# STM32.net
KiCad netlist of a schematic drawn in Altium Designer
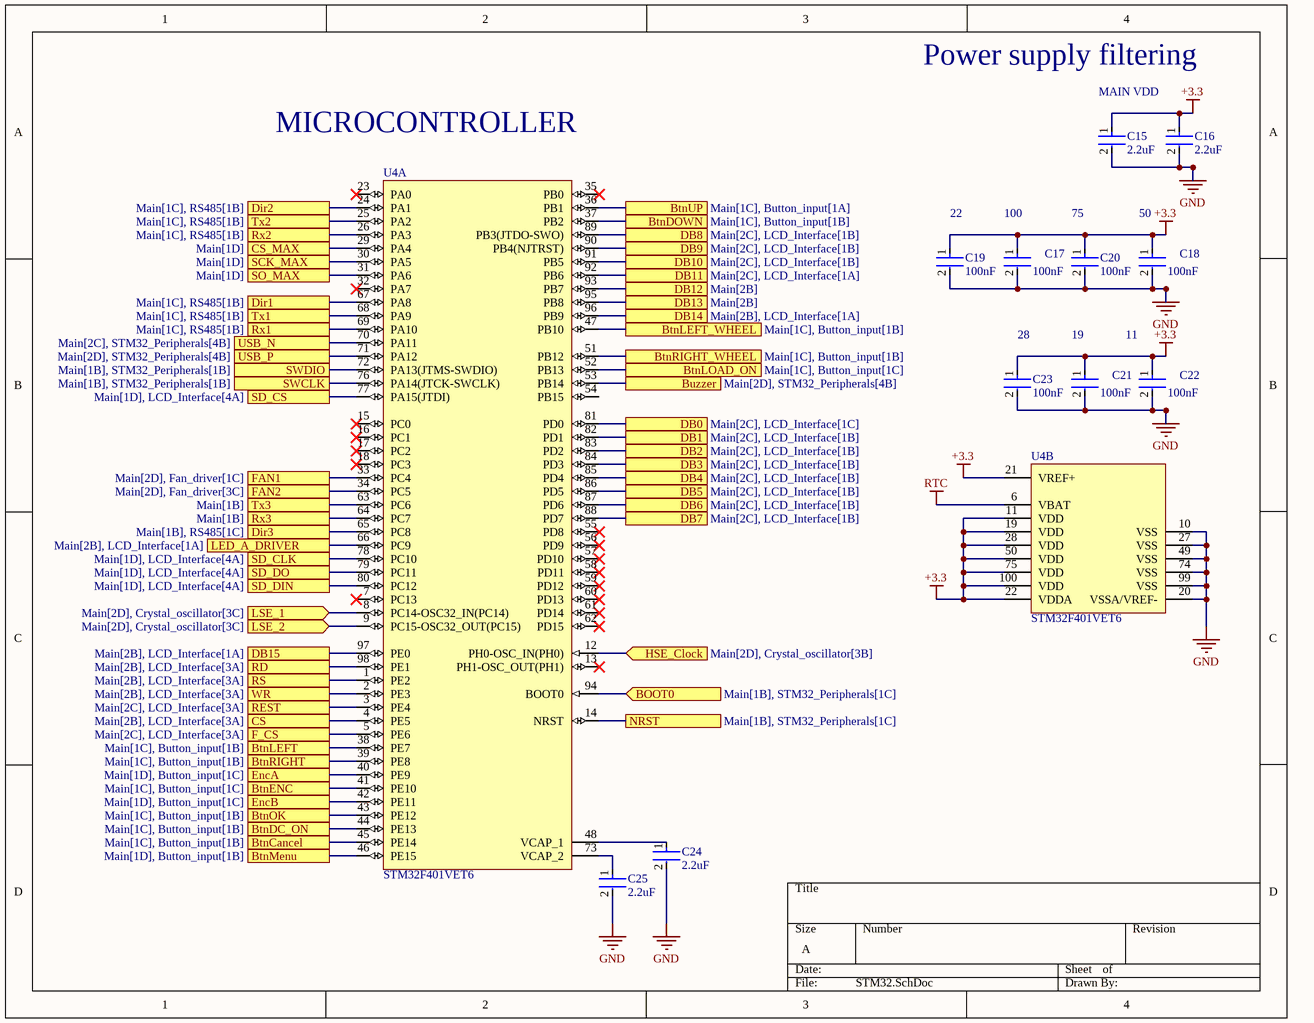
[diagram p0: STM32.SchDoc]

(export (version "E")
  (design (tool "Eeschema 10.0.6"))
  (components
    (comp (ref "C15")
      (value "2.2uF")
      (footprint "FP-0805-L_2_01_0_2-W_1_25-IPC_B")
      (description "General Purpose Ceramic Capacitor, 0805, 10nF, 10%, X7R, 15%, 100V")
      (fields (field (name "VOLTAGE") "100V") (field (name "TOLERANCE") "10%"))
      (libsource (lib "Altium Content Vault") (part "b4654b650e69147ec39a6b967a45e02"))
    )
    (comp (ref "C16")
      (value "2.2uF")
      (footprint "FP-0805-L_2_01_0_2-W_1_25-IPC_B")
      (description "General Purpose Ceramic Capacitor, 0805, 10nF, 10%, X7R, 15%, 100V")
      (fields (field (name "VOLTAGE") "100V") (field (name "TOLERANCE") "10%"))
      (libsource (lib "Altium Content Vault") (part "b4654b650e69147ec39a6b967a45e02"))
    )
    (comp (ref "C17")
      (value "100nF")
      (footprint "FP-CGA3E-0_3-0_1-IPC_A")
      (description "Cap Ceramic 100nF 50V X7R 10% Pad SMD 0603 +125°C Automotive T/R")
      (fields (field (name "TOLERANCE") "10%") (field (name "VOLTAGE") "50V"))
      (libsource (lib "Altium Content Vault") (part "b4654b650e69147ec39a6b967a45e02"))
    )
    (comp (ref "C18")
      (value "100nF")
      (footprint "FP-CGA3E-0_3-0_1-IPC_A")
      (description "Cap Ceramic 100nF 50V X7R 10% Pad SMD 0603 +125°C Automotive T/R")
      (fields (field (name "TOLERANCE") "10%") (field (name "VOLTAGE") "50V"))
      (libsource (lib "Altium Content Vault") (part "b4654b650e69147ec39a6b967a45e02"))
    )
    (comp (ref "C19")
      (value "100nF")
      (footprint "FP-CGA3E-0_3-0_1-IPC_A")
      (description "Cap Ceramic 100nF 50V X7R 10% Pad SMD 0603 +125°C Automotive T/R")
      (fields (field (name "TOLERANCE") "10%") (field (name "VOLTAGE") "50V"))
      (libsource (lib "Altium Content Vault") (part "b4654b650e69147ec39a6b967a45e02"))
    )
    (comp (ref "C20")
      (value "100nF")
      (footprint "FP-CGA3E-0_3-0_1-IPC_A")
      (description "Cap Ceramic 100nF 50V X7R 10% Pad SMD 0603 +125°C Automotive T/R")
      (fields (field (name "TOLERANCE") "10%") (field (name "VOLTAGE") "50V"))
      (libsource (lib "Altium Content Vault") (part "b4654b650e69147ec39a6b967a45e02"))
    )
    (comp (ref "C21")
      (value "100nF")
      (footprint "FP-CGA3E-0_3-0_1-IPC_A")
      (description "Cap Ceramic 100nF 50V X7R 10% Pad SMD 0603 +125°C Automotive T/R")
      (fields (field (name "TOLERANCE") "10%") (field (name "VOLTAGE") "50V"))
      (libsource (lib "Altium Content Vault") (part "b4654b650e69147ec39a6b967a45e02"))
    )
    (comp (ref "C22")
      (value "100nF")
      (footprint "FP-CGA3E-0_3-0_1-IPC_A")
      (description "Cap Ceramic 100nF 50V X7R 10% Pad SMD 0603 +125°C Automotive T/R")
      (fields (field (name "TOLERANCE") "10%") (field (name "VOLTAGE") "50V"))
      (libsource (lib "Altium Content Vault") (part "b4654b650e69147ec39a6b967a45e02"))
    )
    (comp (ref "C23")
      (value "100nF")
      (footprint "FP-CGA3E-0_3-0_1-IPC_A")
      (description "Cap Ceramic 100nF 50V X7R 10% Pad SMD 0603 +125°C Automotive T/R")
      (fields (field (name "TOLERANCE") "10%") (field (name "VOLTAGE") "50V"))
      (libsource (lib "Altium Content Vault") (part "b4654b650e69147ec39a6b967a45e02"))
    )
    (comp (ref "C24")
      (value "2.2uF")
      (footprint "FP-0805-L_2_01_0_2-W_1_25-IPC_B")
      (description "General Purpose Ceramic Capacitor, 0805, 10nF, 10%, X7R, 15%, 100V")
      (fields (field (name "VOLTAGE") "100V") (field (name "TOLERANCE") "10%"))
      (libsource (lib "Altium Content Vault") (part "b4654b650e69147ec39a6b967a45e02"))
    )
    (comp (ref "C25")
      (value "2.2uF")
      (footprint "FP-0805-L_2_01_0_2-W_1_25-IPC_B")
      (description "General Purpose Ceramic Capacitor, 0805, 10nF, 10%, X7R, 15%, 100V")
      (fields (field (name "VOLTAGE") "100V") (field (name "TOLERANCE") "10%"))
      (libsource (lib "Altium Content Vault") (part "b4654b650e69147ec39a6b967a45e02"))
    )
    (comp (ref "U4")
      (value "STM32F401VET6")
      (footprint "STM-LQFP100_L")
      (libsource (lib "Altium Content Vault") (part "MC-ARM-STM32F401-LQFP100"))
    )
  )
  (nets
    (net (code "1") (name "+3.3") (class "Default")
      (node (ref "C15") (pin "1") (pinfunction "1_1") (pintype "passive"))
      (node (ref "C16") (pin "1") (pinfunction "1_1") (pintype "passive"))
      (node (ref "C17") (pin "1") (pinfunction "1_1") (pintype "passive"))
      (node (ref "C18") (pin "1") (pinfunction "1_1") (pintype "passive"))
      (node (ref "C19") (pin "1") (pinfunction "1_1") (pintype "passive"))
      (node (ref "C20") (pin "1") (pinfunction "1_1") (pintype "passive"))
      (node (ref "C21") (pin "1") (pinfunction "1_1") (pintype "passive"))
      (node (ref "C22") (pin "1") (pinfunction "1_1") (pintype "passive"))
      (node (ref "C23") (pin "1") (pinfunction "1_1") (pintype "passive"))
      (node (ref "U4") (pin "100") (pinfunction "VDD_100") (pintype "power_in"))
      (node (ref "U4") (pin "11") (pinfunction "VDD_11") (pintype "power_in"))
      (node (ref "U4") (pin "19") (pinfunction "VDD_19") (pintype "power_in"))
      (node (ref "U4") (pin "21") (pinfunction "VREF+_21") (pintype "power_in"))
      (node (ref "U4") (pin "22") (pinfunction "VDDA_22") (pintype "power_in"))
      (node (ref "U4") (pin "28") (pinfunction "VDD_28") (pintype "power_in"))
      (node (ref "U4") (pin "50") (pinfunction "VDD_50") (pintype "power_in"))
      (node (ref "U4") (pin "75") (pinfunction "VDD_75") (pintype "power_in"))
    )
    (net (code "2") (name "/BOOT0") (class "Default")
      (node (ref "U4") (pin "94") (pinfunction "BOOT0_94") (pintype "input"))
    )
    (net (code "3") (name "/BtnCancel") (class "Default")
      (node (ref "U4") (pin "45") (pinfunction "PE14_45") (pintype "bidirectional"))
    )
    (net (code "4") (name "/BtnDC_ON") (class "Default")
      (node (ref "U4") (pin "44") (pinfunction "PE13_44") (pintype "bidirectional"))
    )
    (net (code "5") (name "/BtnDOWN") (class "Default")
      (node (ref "U4") (pin "37") (pinfunction "PB2_37") (pintype "bidirectional"))
    )
    (net (code "6") (name "/BtnENC") (class "Default")
      (node (ref "U4") (pin "41") (pinfunction "PE10_41") (pintype "bidirectional"))
    )
    (net (code "7") (name "/BtnLEFT") (class "Default")
      (node (ref "U4") (pin "38") (pinfunction "PE7_38") (pintype "bidirectional"))
    )
    (net (code "8") (name "/BtnLEFT_WHEEL") (class "Default")
      (node (ref "U4") (pin "47") (pinfunction "PB10_47") (pintype "bidirectional"))
    )
    (net (code "9") (name "/BtnLOAD_ON") (class "Default")
      (node (ref "U4") (pin "52") (pinfunction "PB13_52") (pintype "bidirectional"))
    )
    (net (code "10") (name "/BtnMenu") (class "Default")
      (node (ref "U4") (pin "46") (pinfunction "PE15_46") (pintype "bidirectional"))
    )
    (net (code "11") (name "/BtnOK") (class "Default")
      (node (ref "U4") (pin "43") (pinfunction "PE12_43") (pintype "bidirectional"))
    )
    (net (code "12") (name "/BtnRIGHT") (class "Default")
      (node (ref "U4") (pin "39") (pinfunction "PE8_39") (pintype "bidirectional"))
    )
    (net (code "13") (name "/BtnRIGHT_WHEEL") (class "Default")
      (node (ref "U4") (pin "51") (pinfunction "PB12_51") (pintype "bidirectional"))
    )
    (net (code "14") (name "/BtnUP") (class "Default")
      (node (ref "U4") (pin "36") (pinfunction "PB1_36") (pintype "bidirectional"))
    )
    (net (code "15") (name "/Buzzer") (class "Default")
      (node (ref "U4") (pin "53") (pinfunction "PB14_53") (pintype "bidirectional"))
    )
    (net (code "16") (name "/CS") (class "Default")
      (node (ref "U4") (pin "4") (pinfunction "PE5_4") (pintype "bidirectional"))
    )
    (net (code "17") (name "/CS_MAX") (class "Default")
      (node (ref "U4") (pin "29") (pinfunction "PA4_29") (pintype "bidirectional"))
    )
    (net (code "18") (name "/DB0") (class "Default")
      (node (ref "U4") (pin "81") (pinfunction "PD0_81") (pintype "bidirectional"))
    )
    (net (code "19") (name "/DB1") (class "Default")
      (node (ref "U4") (pin "82") (pinfunction "PD1_82") (pintype "bidirectional"))
    )
    (net (code "20") (name "/DB2") (class "Default")
      (node (ref "U4") (pin "83") (pinfunction "PD2_83") (pintype "bidirectional"))
    )
    (net (code "21") (name "/DB3") (class "Default")
      (node (ref "U4") (pin "84") (pinfunction "PD3_84") (pintype "bidirectional"))
    )
    (net (code "22") (name "/DB4") (class "Default")
      (node (ref "U4") (pin "85") (pinfunction "PD4_85") (pintype "bidirectional"))
    )
    (net (code "23") (name "/DB5") (class "Default")
      (node (ref "U4") (pin "86") (pinfunction "PD5_86") (pintype "bidirectional"))
    )
    (net (code "24") (name "/DB6") (class "Default")
      (node (ref "U4") (pin "87") (pinfunction "PD6_87") (pintype "bidirectional"))
    )
    (net (code "25") (name "/DB7") (class "Default")
      (node (ref "U4") (pin "88") (pinfunction "PD7_88") (pintype "bidirectional"))
    )
    (net (code "26") (name "/DB8") (class "Default")
      (node (ref "U4") (pin "89") (pinfunction "PB3(JTDO-SWO)_89") (pintype "bidirectional"))
    )
    (net (code "27") (name "/DB9") (class "Default")
      (node (ref "U4") (pin "90") (pinfunction "PB4(NJTRST)_90") (pintype "bidirectional"))
    )
    (net (code "28") (name "/DB10") (class "Default")
      (node (ref "U4") (pin "91") (pinfunction "PB5_91") (pintype "bidirectional"))
    )
    (net (code "29") (name "/DB11") (class "Default")
      (node (ref "U4") (pin "92") (pinfunction "PB6_92") (pintype "bidirectional"))
    )
    (net (code "30") (name "/DB12") (class "Default")
      (node (ref "U4") (pin "93") (pinfunction "PB7_93") (pintype "bidirectional"))
    )
    (net (code "31") (name "/DB13") (class "Default")
      (node (ref "U4") (pin "95") (pinfunction "PB8_95") (pintype "bidirectional"))
    )
    (net (code "32") (name "/DB14") (class "Default")
      (node (ref "U4") (pin "96") (pinfunction "PB9_96") (pintype "bidirectional"))
    )
    (net (code "33") (name "/DB15") (class "Default")
      (node (ref "U4") (pin "97") (pinfunction "PE0_97") (pintype "bidirectional"))
    )
    (net (code "34") (name "/Dir1") (class "Default")
      (node (ref "U4") (pin "67") (pinfunction "PA8_67") (pintype "bidirectional"))
    )
    (net (code "35") (name "/Dir2") (class "Default")
      (node (ref "U4") (pin "24") (pinfunction "PA1_24") (pintype "bidirectional"))
    )
    (net (code "36") (name "/Dir3") (class "Default")
      (node (ref "U4") (pin "65") (pinfunction "PC8_65") (pintype "bidirectional"))
    )
    (net (code "37") (name "/EncA") (class "Default")
      (node (ref "U4") (pin "40") (pinfunction "PE9_40") (pintype "bidirectional"))
    )
    (net (code "38") (name "/EncB") (class "Default")
      (node (ref "U4") (pin "42") (pinfunction "PE11_42") (pintype "bidirectional"))
    )
    (net (code "39") (name "/FAN1") (class "Default")
      (node (ref "U4") (pin "33") (pinfunction "PC4_33") (pintype "bidirectional"))
    )
    (net (code "40") (name "/FAN2") (class "Default")
      (node (ref "U4") (pin "34") (pinfunction "PC5_34") (pintype "bidirectional"))
    )
    (net (code "41") (name "/F_CS") (class "Default")
      (node (ref "U4") (pin "5") (pinfunction "PE6_5") (pintype "bidirectional"))
    )
    (net (code "42") (name "/HSE_Clock") (class "Default")
      (node (ref "U4") (pin "12") (pinfunction "PH0-OSC_IN(PH0)_12") (pintype "input"))
    )
    (net (code "43") (name "/LED_A_DRIVER") (class "Default")
      (node (ref "U4") (pin "66") (pinfunction "PC9_66") (pintype "bidirectional"))
    )
    (net (code "44") (name "/LSE_1") (class "Default")
      (node (ref "U4") (pin "8") (pinfunction "PC14-OSC32_IN(PC14)_8") (pintype "bidirectional"))
    )
    (net (code "45") (name "/LSE_2") (class "Default")
      (node (ref "U4") (pin "9") (pinfunction "PC15-OSC32_OUT(PC15)_9") (pintype "bidirectional"))
    )
    (net (code "46") (name "/NRST") (class "Default")
      (node (ref "U4") (pin "14") (pinfunction "NRST_14") (pintype "bidirectional"))
    )
    (net (code "47") (name "/RD") (class "Default")
      (node (ref "U4") (pin "98") (pinfunction "PE1_98") (pintype "bidirectional"))
    )
    (net (code "48") (name "/REST") (class "Default")
      (node (ref "U4") (pin "3") (pinfunction "PE4_3") (pintype "bidirectional"))
    )
    (net (code "49") (name "/RS") (class "Default")
      (node (ref "U4") (pin "1") (pinfunction "PE2_1") (pintype "bidirectional"))
    )
    (net (code "50") (name "/Rx1") (class "Default")
      (node (ref "U4") (pin "69") (pinfunction "PA10_69") (pintype "bidirectional"))
    )
    (net (code "51") (name "/Rx2") (class "Default")
      (node (ref "U4") (pin "26") (pinfunction "PA3_26") (pintype "bidirectional"))
    )
    (net (code "52") (name "/Rx3") (class "Default")
      (node (ref "U4") (pin "64") (pinfunction "PC7_64") (pintype "bidirectional"))
    )
    (net (code "53") (name "/SCK_MAX") (class "Default")
      (node (ref "U4") (pin "30") (pinfunction "PA5_30") (pintype "bidirectional"))
    )
    (net (code "54") (name "/SD_CLK") (class "Default")
      (node (ref "U4") (pin "78") (pinfunction "PC10_78") (pintype "bidirectional"))
    )
    (net (code "55") (name "/SD_CS") (class "Default")
      (node (ref "U4") (pin "77") (pinfunction "PA15(JTDI)_77") (pintype "bidirectional"))
    )
    (net (code "56") (name "/SD_DIN") (class "Default")
      (node (ref "U4") (pin "80") (pinfunction "PC12_80") (pintype "bidirectional"))
    )
    (net (code "57") (name "/SD_DO") (class "Default")
      (node (ref "U4") (pin "79") (pinfunction "PC11_79") (pintype "bidirectional"))
    )
    (net (code "58") (name "/SO_MAX") (class "Default")
      (node (ref "U4") (pin "31") (pinfunction "PA6_31") (pintype "bidirectional"))
    )
    (net (code "59") (name "/SWCLK") (class "Default")
      (node (ref "U4") (pin "76") (pinfunction "PA14(JTCK-SWCLK)_76") (pintype "bidirectional"))
    )
    (net (code "60") (name "/SWDIO") (class "Default")
      (node (ref "U4") (pin "72") (pinfunction "PA13(JTMS-SWDIO)_72") (pintype "bidirectional"))
    )
    (net (code "61") (name "/Tx1") (class "Default")
      (node (ref "U4") (pin "68") (pinfunction "PA9_68") (pintype "bidirectional"))
    )
    (net (code "62") (name "/Tx2") (class "Default")
      (node (ref "U4") (pin "25") (pinfunction "PA2_25") (pintype "bidirectional"))
    )
    (net (code "63") (name "/Tx3") (class "Default")
      (node (ref "U4") (pin "63") (pinfunction "PC6_63") (pintype "bidirectional"))
    )
    (net (code "64") (name "/USB_N") (class "Default")
      (node (ref "U4") (pin "70") (pinfunction "PA11_70") (pintype "bidirectional"))
    )
    (net (code "65") (name "/USB_P") (class "Default")
      (node (ref "U4") (pin "71") (pinfunction "PA12_71") (pintype "bidirectional"))
    )
    (net (code "66") (name "/WR") (class "Default")
      (node (ref "U4") (pin "2") (pinfunction "PE3_2") (pintype "bidirectional"))
    )
    (net (code "67") (name "GND") (class "Default")
      (node (ref "C15") (pin "2") (pinfunction "2_2") (pintype "passive"))
      (node (ref "C16") (pin "2") (pinfunction "2_2") (pintype "passive"))
      (node (ref "C17") (pin "2") (pinfunction "2_2") (pintype "passive"))
      (node (ref "C18") (pin "2") (pinfunction "2_2") (pintype "passive"))
      (node (ref "C19") (pin "2") (pinfunction "2_2") (pintype "passive"))
      (node (ref "C20") (pin "2") (pinfunction "2_2") (pintype "passive"))
      (node (ref "C21") (pin "2") (pinfunction "2_2") (pintype "passive"))
      (node (ref "C22") (pin "2") (pinfunction "2_2") (pintype "passive"))
      (node (ref "C23") (pin "2") (pinfunction "2_2") (pintype "passive"))
      (node (ref "C24") (pin "2") (pinfunction "2_2") (pintype "passive"))
      (node (ref "C25") (pin "2") (pinfunction "2_2") (pintype "passive"))
      (node (ref "U4") (pin "10") (pinfunction "VSS_10") (pintype "power_in"))
      (node (ref "U4") (pin "20") (pinfunction "VSSA/VREF-_20") (pintype "power_in"))
      (node (ref "U4") (pin "27") (pinfunction "VSS_27") (pintype "power_in"))
      (node (ref "U4") (pin "49") (pinfunction "VSS_49") (pintype "power_in"))
      (node (ref "U4") (pin "74") (pinfunction "VSS_74") (pintype "power_in"))
      (node (ref "U4") (pin "99") (pinfunction "VSS_99") (pintype "power_in"))
    )
    (net (code "68") (name "Net-(U4A-VCAP_1)") (class "Default")
      (node (ref "C24") (pin "1") (pinfunction "1_1") (pintype "passive"))
      (node (ref "U4") (pin "48") (pinfunction "VCAP_1_48") (pintype "passive"))
    )
    (net (code "69") (name "Net-(U4A-VCAP_2)") (class "Default")
      (node (ref "C25") (pin "1") (pinfunction "1_1") (pintype "passive"))
      (node (ref "U4") (pin "73") (pinfunction "VCAP_2_73") (pintype "passive"))
    )
    (net (code "70") (name "RTC") (class "Default")
      (node (ref "U4") (pin "6") (pinfunction "VBAT_6") (pintype "power_in"))
    )
    (net (code "71") (name "unconnected-(U4A-PA0-Pad23)") (class "Default")
      (node (ref "U4") (pin "23") (pinfunction "PA0_23") (pintype "bidirectional+no_connect"))
    )
    (net (code "72") (name "unconnected-(U4A-PA7-Pad32)") (class "Default")
      (node (ref "U4") (pin "32") (pinfunction "PA7_32") (pintype "bidirectional+no_connect"))
    )
    (net (code "73") (name "unconnected-(U4A-PB0-Pad35)") (class "Default")
      (node (ref "U4") (pin "35") (pinfunction "PB0_35") (pintype "bidirectional+no_connect"))
    )
    (net (code "74") (name "unconnected-(U4A-PB15-Pad54)") (class "Default")
      (node (ref "U4") (pin "54") (pinfunction "PB15_54") (pintype "bidirectional"))
    )
    (net (code "75") (name "unconnected-(U4A-PC0-Pad15)") (class "Default")
      (node (ref "U4") (pin "15") (pinfunction "PC0_15") (pintype "bidirectional+no_connect"))
    )
    (net (code "76") (name "unconnected-(U4A-PC1-Pad16)") (class "Default")
      (node (ref "U4") (pin "16") (pinfunction "PC1_16") (pintype "bidirectional+no_connect"))
    )
    (net (code "77") (name "unconnected-(U4A-PC2-Pad17)") (class "Default")
      (node (ref "U4") (pin "17") (pinfunction "PC2_17") (pintype "bidirectional+no_connect"))
    )
    (net (code "78") (name "unconnected-(U4A-PC3-Pad18)") (class "Default")
      (node (ref "U4") (pin "18") (pinfunction "PC3_18") (pintype "bidirectional+no_connect"))
    )
    (net (code "79") (name "unconnected-(U4A-PC13-Pad7)") (class "Default")
      (node (ref "U4") (pin "7") (pinfunction "PC13_7") (pintype "bidirectional+no_connect"))
    )
    (net (code "80") (name "unconnected-(U4A-PD8-Pad55)") (class "Default")
      (node (ref "U4") (pin "55") (pinfunction "PD8_55") (pintype "bidirectional+no_connect"))
    )
    (net (code "81") (name "unconnected-(U4A-PD9-Pad56)") (class "Default")
      (node (ref "U4") (pin "56") (pinfunction "PD9_56") (pintype "bidirectional+no_connect"))
    )
    (net (code "82") (name "unconnected-(U4A-PD10-Pad57)") (class "Default")
      (node (ref "U4") (pin "57") (pinfunction "PD10_57") (pintype "bidirectional+no_connect"))
    )
    (net (code "83") (name "unconnected-(U4A-PD11-Pad58)") (class "Default")
      (node (ref "U4") (pin "58") (pinfunction "PD11_58") (pintype "bidirectional+no_connect"))
    )
    (net (code "84") (name "unconnected-(U4A-PD12-Pad59)") (class "Default")
      (node (ref "U4") (pin "59") (pinfunction "PD12_59") (pintype "bidirectional+no_connect"))
    )
    (net (code "85") (name "unconnected-(U4A-PD13-Pad60)") (class "Default")
      (node (ref "U4") (pin "60") (pinfunction "PD13_60") (pintype "bidirectional+no_connect"))
    )
    (net (code "86") (name "unconnected-(U4A-PD14-Pad61)") (class "Default")
      (node (ref "U4") (pin "61") (pinfunction "PD14_61") (pintype "bidirectional+no_connect"))
    )
    (net (code "87") (name "unconnected-(U4A-PD15-Pad62)") (class "Default")
      (node (ref "U4") (pin "62") (pinfunction "PD15_62") (pintype "bidirectional+no_connect"))
    )
    (net (code "88") (name "unconnected-(U4A-PH1-OSC_OUT(PH1)-Pad13)") (class "Default")
      (node (ref "U4") (pin "13") (pinfunction "PH1-OSC_OUT(PH1)_13") (pintype "bidirectional+no_connect"))
    )
  )
)
